# Spring2020.net
KiCad netlist of a schematic drawn in EAGLE
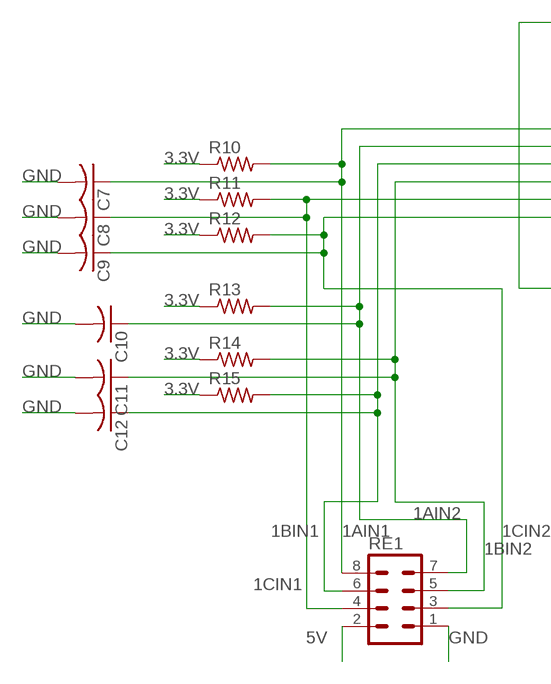
[diagram p0: schematic, sheet 1, part 1 of 2]
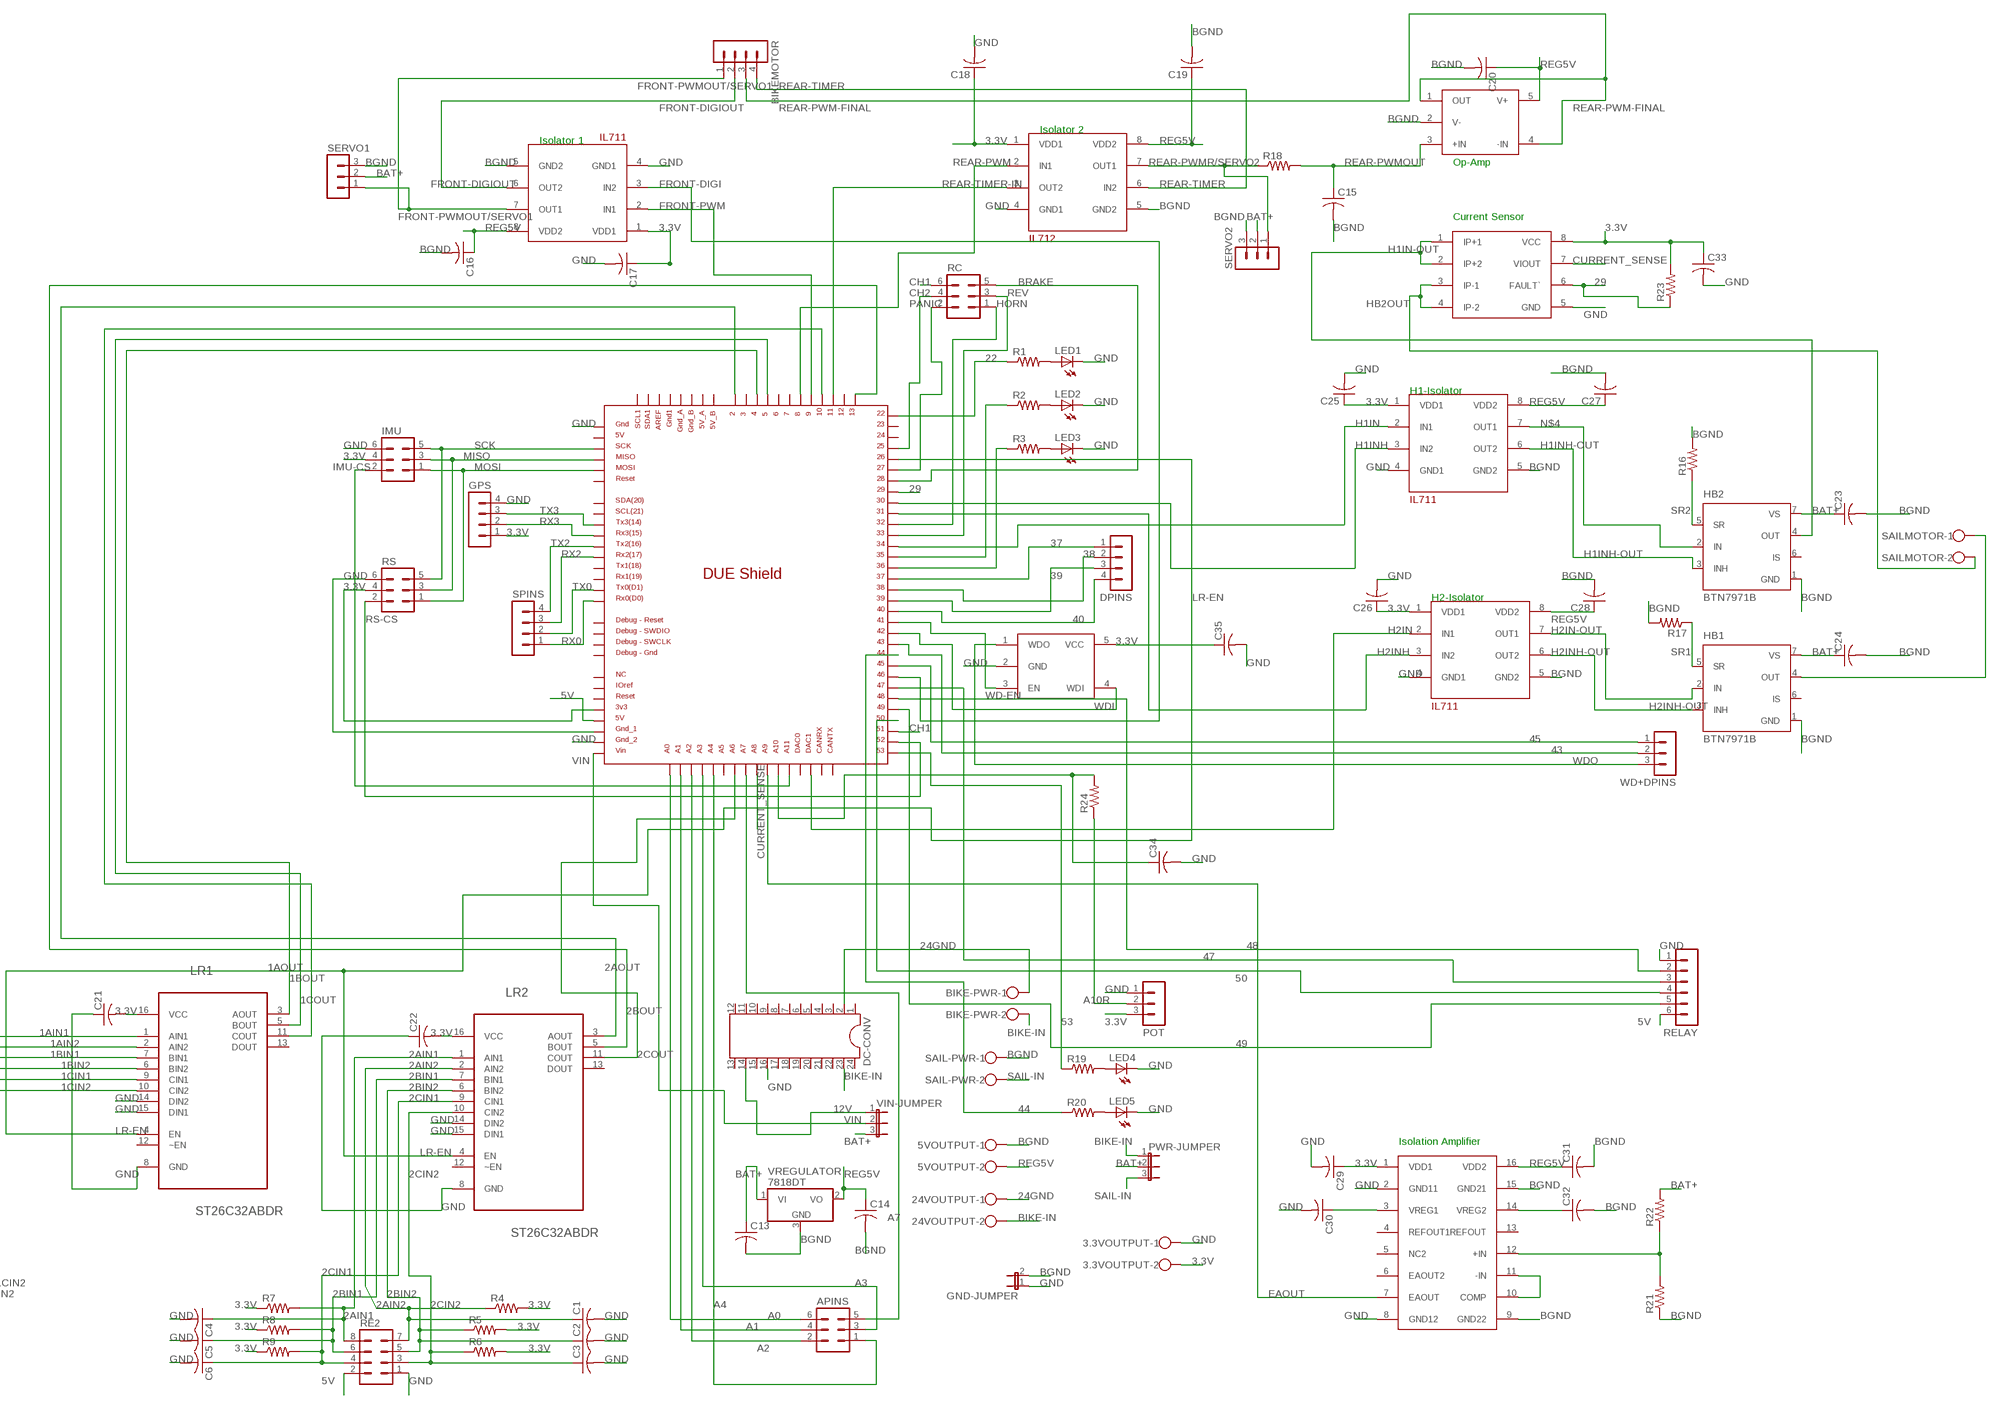
[diagram p1: schematic, sheet 1, part 2 of 2]

(export (version "E")
  (design (tool "Eeschema 10.0.6"))
  (components
    (comp (ref "3.3VOUTPUT")
      (value "W237-102")
      (footprint "eagle-import:W237-102")
      (fields (field (name "MPN") "237-102"))
      (libsource (lib "eagle-import") (part "W237-102"))
    )
    (comp (ref "5VOUTPUT")
      (value "W237-102")
      (footprint "eagle-import:W237-102")
      (fields (field (name "MPN") "237-102"))
      (libsource (lib "eagle-import") (part "W237-102"))
    )
    (comp (ref "24VOUTPUT")
      (value "W237-102")
      (footprint "eagle-import:W237-102")
      (fields (field (name "MPN") "237-102"))
      (libsource (lib "eagle-import") (part "W237-102"))
    )
    (comp (ref "APINS")
      (value "MA03-2")
      (footprint "eagle-import:MA03-2")
      (libsource (lib "eagle-import") (part "MA03-2"))
    )
    (comp (ref "BIKE-PWR")
      (value "W237-102")
      (footprint "eagle-import:W237-102")
      (fields (field (name "MPN") "237-102"))
      (libsource (lib "eagle-import") (part "W237-102"))
    )
    (comp (ref "BIKEMOTOR")
      (value "MA04-1")
      (footprint "eagle-import:MA04-1")
      (libsource (lib "eagle-import") (part "MA04-1"))
    )
    (comp (ref "C1")
      (value "C-US025-025X050")
      (footprint "eagle-import:C025-025X050")
      (libsource (lib "eagle-import") (part "C-US025-025X050"))
    )
    (comp (ref "C2")
      (value "C-US025-025X050")
      (footprint "eagle-import:C025-025X050")
      (libsource (lib "eagle-import") (part "C-US025-025X050"))
    )
    (comp (ref "C3")
      (value "C-US025-025X050")
      (footprint "eagle-import:C025-025X050")
      (libsource (lib "eagle-import") (part "C-US025-025X050"))
    )
    (comp (ref "C4")
      (value "C-US025-025X050")
      (footprint "eagle-import:C025-025X050")
      (libsource (lib "eagle-import") (part "C-US025-025X050"))
    )
    (comp (ref "C5")
      (value "C-US025-025X050")
      (footprint "eagle-import:C025-025X050")
      (libsource (lib "eagle-import") (part "C-US025-025X050"))
    )
    (comp (ref "C6")
      (value "C-US025-025X050")
      (footprint "eagle-import:C025-025X050")
      (libsource (lib "eagle-import") (part "C-US025-025X050"))
    )
    (comp (ref "C7")
      (value "C-US025-025X050")
      (footprint "eagle-import:C025-025X050")
      (libsource (lib "eagle-import") (part "C-US025-025X050"))
    )
    (comp (ref "C8")
      (value "C-US025-025X050")
      (footprint "eagle-import:C025-025X050")
      (libsource (lib "eagle-import") (part "C-US025-025X050"))
    )
    (comp (ref "C9")
      (value "C-US025-025X050")
      (footprint "eagle-import:C025-025X050")
      (libsource (lib "eagle-import") (part "C-US025-025X050"))
    )
    (comp (ref "C10")
      (value "C-US025-025X050")
      (footprint "eagle-import:C025-025X050")
      (libsource (lib "eagle-import") (part "C-US025-025X050"))
    )
    (comp (ref "C11")
      (value "C-US025-025X050")
      (footprint "eagle-import:C025-025X050")
      (libsource (lib "eagle-import") (part "C-US025-025X050"))
    )
    (comp (ref "C12")
      (value "C-US025-025X050")
      (footprint "eagle-import:C025-025X050")
      (libsource (lib "eagle-import") (part "C-US025-025X050"))
    )
    (comp (ref "C13")
      (value "C-US025-050X050")
      (footprint "eagle-import:C025-050X050")
      (libsource (lib "eagle-import") (part "C-US025-050X050"))
    )
    (comp (ref "C14")
      (value "C-US025-050X050")
      (footprint "eagle-import:C025-050X050")
      (libsource (lib "eagle-import") (part "C-US025-050X050"))
    )
    (comp (ref "C15")
      (value "C-US025-050X050")
      (footprint "eagle-import:C025-050X050")
      (libsource (lib "eagle-import") (part "C-US025-050X050"))
    )
    (comp (ref "C16")
      (value "C-US025-050X050")
      (footprint "eagle-import:C025-050X050")
      (libsource (lib "eagle-import") (part "C-US025-050X050"))
    )
    (comp (ref "C17")
      (value "C-US025-050X050")
      (footprint "eagle-import:C025-050X050")
      (libsource (lib "eagle-import") (part "C-US025-050X050"))
    )
    (comp (ref "C18")
      (value "C-US025-050X050")
      (footprint "eagle-import:C025-050X050")
      (libsource (lib "eagle-import") (part "C-US025-050X050"))
    )
    (comp (ref "C19")
      (value "C-US025-050X050")
      (footprint "eagle-import:C025-050X050")
      (libsource (lib "eagle-import") (part "C-US025-050X050"))
    )
    (comp (ref "C20")
      (value "C-US025-050X050")
      (footprint "eagle-import:C025-050X050")
      (libsource (lib "eagle-import") (part "C-US025-050X050"))
    )
    (comp (ref "C21")
      (value "C-US025-050X050")
      (footprint "eagle-import:C025-050X050")
      (libsource (lib "eagle-import") (part "C-US025-050X050"))
    )
    (comp (ref "C22")
      (value "C-US025-050X050")
      (footprint "eagle-import:C025-050X050")
      (libsource (lib "eagle-import") (part "C-US025-050X050"))
    )
    (comp (ref "C23")
      (value "C-US150-091X182")
      (footprint "eagle-import:C150-091X182")
      (libsource (lib "eagle-import") (part "C-US150-091X182"))
    )
    (comp (ref "C24")
      (value "C-US150-091X182")
      (footprint "eagle-import:C150-091X182")
      (libsource (lib "eagle-import") (part "C-US150-091X182"))
    )
    (comp (ref "C25")
      (value "C-US025-050X050")
      (footprint "eagle-import:C025-050X050")
      (libsource (lib "eagle-import") (part "C-US025-050X050"))
    )
    (comp (ref "C26")
      (value "C-US025-050X050")
      (footprint "eagle-import:C025-050X050")
      (libsource (lib "eagle-import") (part "C-US025-050X050"))
    )
    (comp (ref "C27")
      (value "C-US025-050X050")
      (footprint "eagle-import:C025-050X050")
      (libsource (lib "eagle-import") (part "C-US025-050X050"))
    )
    (comp (ref "C28")
      (value "C-US025-050X050")
      (footprint "eagle-import:C025-050X050")
      (libsource (lib "eagle-import") (part "C-US025-050X050"))
    )
    (comp (ref "C29")
      (value "C-US025-050X050")
      (footprint "eagle-import:C025-050X050")
      (libsource (lib "eagle-import") (part "C-US025-050X050"))
    )
    (comp (ref "C30")
      (value "C-US025-050X050")
      (footprint "eagle-import:C025-050X050")
      (libsource (lib "eagle-import") (part "C-US025-050X050"))
    )
    (comp (ref "C31")
      (value "C-US025-050X050")
      (footprint "eagle-import:C025-050X050")
      (libsource (lib "eagle-import") (part "C-US025-050X050"))
    )
    (comp (ref "C32")
      (value "C-US025-050X050")
      (footprint "eagle-import:C025-050X050")
      (libsource (lib "eagle-import") (part "C-US025-050X050"))
    )
    (comp (ref "C33")
      (value "C-US025-050X050")
      (footprint "eagle-import:C025-050X050")
      (libsource (lib "eagle-import") (part "C-US025-050X050"))
    )
    (comp (ref "C34")
      (value "C-US025-050X050")
      (footprint "eagle-import:C025-050X050")
      (libsource (lib "eagle-import") (part "C-US025-050X050"))
    )
    (comp (ref "C35")
      (value "C-US025-025X050")
      (footprint "eagle-import:C025-025X050")
      (libsource (lib "eagle-import") (part "C-US025-025X050"))
    )
    (comp (ref "DC-CONV")
      (value "CU.INC---VAWQ6-Q48-S12H-6")
      (footprint "eagle-import:DIL24-6")
      (libsource (lib "eagle-import") (part "CU.INC---VAWQ6-Q48-S12H-6"))
    )
    (comp (ref "DPINS")
      (value "MA04-1")
      (footprint "eagle-import:MA04-1")
      (libsource (lib "eagle-import") (part "MA04-1"))
    )
    (comp (ref "GND-JUMPER")
      (value "JP1E")
      (footprint "eagle-import:JP1")
      (libsource (lib "eagle-import") (part "JP1E"))
    )
    (comp (ref "GPS")
      (value "MA04-1")
      (footprint "eagle-import:MA04-1")
      (libsource (lib "eagle-import") (part "MA04-1"))
    )
    (comp (ref "HB1")
      (value "BTN7971B")
      (footprint "eagle-import:P-TO263-7-1")
      (libsource (lib "eagle-import") (part "BTN7971B"))
    )
    (comp (ref "HB2")
      (value "BTN7971B")
      (footprint "eagle-import:P-TO263-7-1")
      (libsource (lib "eagle-import") (part "BTN7971B"))
    )
    (comp (ref "IMU")
      (value "MA03-2")
      (footprint "eagle-import:MA03-2")
      (libsource (lib "eagle-import") (part "MA03-2"))
    )
    (comp (ref "LED1")
      (value "LED5MM")
      (footprint "eagle-import:LED5MM")
      (libsource (lib "eagle-import") (part "LED5MM"))
    )
    (comp (ref "LED2")
      (value "LED5MM")
      (footprint "eagle-import:LED5MM")
      (libsource (lib "eagle-import") (part "LED5MM"))
    )
    (comp (ref "LED3")
      (value "LED5MM")
      (footprint "eagle-import:LED5MM")
      (libsource (lib "eagle-import") (part "LED5MM"))
    )
    (comp (ref "LED4")
      (value "LED5MM")
      (footprint "eagle-import:LED5MM")
      (libsource (lib "eagle-import") (part "LED5MM"))
    )
    (comp (ref "LED5")
      (value "LED5MM")
      (footprint "eagle-import:LED5MM")
      (libsource (lib "eagle-import") (part "LED5MM"))
    )
    (comp (ref "LR1")
      (value "ST26C32ABDR")
      (footprint "eagle-import:SOIC127P600X175-16N")
      (libsource (lib "eagle-import") (part "ST26C32ABDR"))
    )
    (comp (ref "LR2")
      (value "ST26C32ABDR")
      (footprint "eagle-import:SOIC127P600X175-16N")
      (libsource (lib "eagle-import") (part "ST26C32ABDR"))
    )
    (comp (ref "OP-AMP")
      (value "OPAMP")
      (footprint "eagle-import:SOT95P280X145-5N")
      (libsource (lib "eagle-import") (part "OPAMP"))
    )
    (comp (ref "POT")
      (value "MA03-1")
      (footprint "eagle-import:MA03-1")
      (libsource (lib "eagle-import") (part "MA03-1"))
    )
    (comp (ref "PWR-JUMPER")
      (value "JP2E")
      (footprint "eagle-import:JP2")
      (libsource (lib "eagle-import") (part "JP2E"))
    )
    (comp (ref "R1")
      (value "R-US_0309/10")
      (footprint "eagle-import:0309_10")
      (libsource (lib "eagle-import") (part "R-US_0309/10"))
    )
    (comp (ref "R2")
      (value "R-US_0309/10")
      (footprint "eagle-import:0309_10")
      (libsource (lib "eagle-import") (part "R-US_0309/10"))
    )
    (comp (ref "R3")
      (value "R-US_0309/10")
      (footprint "eagle-import:0309_10")
      (libsource (lib "eagle-import") (part "R-US_0309/10"))
    )
    (comp (ref "R4")
      (value "R-US_0613/15")
      (footprint "eagle-import:P0613_15")
      (libsource (lib "eagle-import") (part "resistor_R-US_0613/15"))
    )
    (comp (ref "R5")
      (value "R-US_0613/15")
      (footprint "eagle-import:P0613_15")
      (libsource (lib "eagle-import") (part "resistor_R-US_0613/15"))
    )
    (comp (ref "R6")
      (value "R-US_0613/15")
      (footprint "eagle-import:P0613_15")
      (libsource (lib "eagle-import") (part "resistor_R-US_0613/15"))
    )
    (comp (ref "R7")
      (value "R-US_0613/15")
      (footprint "eagle-import:P0613_15")
      (libsource (lib "eagle-import") (part "resistor_R-US_0613/15"))
    )
    (comp (ref "R8")
      (value "R-US_0613/15")
      (footprint "eagle-import:P0613_15")
      (libsource (lib "eagle-import") (part "resistor_R-US_0613/15"))
    )
    (comp (ref "R9")
      (value "R-US_0613/15")
      (footprint "eagle-import:P0613_15")
      (libsource (lib "eagle-import") (part "resistor_R-US_0613/15"))
    )
    (comp (ref "R10")
      (value "R-US_0613/15")
      (footprint "eagle-import:P0613_15")
      (libsource (lib "eagle-import") (part "resistor_R-US_0613/15"))
    )
    (comp (ref "R11")
      (value "R-US_0613/15")
      (footprint "eagle-import:P0613_15")
      (libsource (lib "eagle-import") (part "resistor_R-US_0613/15"))
    )
    (comp (ref "R12")
      (value "R-US_0613/15")
      (footprint "eagle-import:P0613_15")
      (libsource (lib "eagle-import") (part "resistor_R-US_0613/15"))
    )
    (comp (ref "R13")
      (value "R-US_0613/15")
      (footprint "eagle-import:P0613_15")
      (libsource (lib "eagle-import") (part "resistor_R-US_0613/15"))
    )
    (comp (ref "R14")
      (value "R-US_0613/15")
      (footprint "eagle-import:P0613_15")
      (libsource (lib "eagle-import") (part "resistor_R-US_0613/15"))
    )
    (comp (ref "R15")
      (value "R-US_0613/15")
      (footprint "eagle-import:P0613_15")
      (libsource (lib "eagle-import") (part "resistor_R-US_0613/15"))
    )
    (comp (ref "R16")
      (value "R-US_0613/15")
      (footprint "eagle-import:P0613_15")
      (libsource (lib "eagle-import") (part "resistor_R-US_0613/15"))
    )
    (comp (ref "R17")
      (value "R-US_0613/15")
      (footprint "eagle-import:P0613_15")
      (libsource (lib "eagle-import") (part "resistor_R-US_0613/15"))
    )
    (comp (ref "R18")
      (value "R-US_0414/15")
      (footprint "eagle-import:0414_15")
      (libsource (lib "eagle-import") (part "resistor_R-US_0414/15"))
    )
    (comp (ref "R19")
      (value "R-US_0309/10")
      (footprint "eagle-import:0309_10")
      (libsource (lib "eagle-import") (part "R-US_0309/10"))
    )
    (comp (ref "R20")
      (value "R-US_0309/10")
      (footprint "eagle-import:0309_10")
      (libsource (lib "eagle-import") (part "R-US_0309/10"))
    )
    (comp (ref "R21")
      (value "R-US_0414/15")
      (footprint "eagle-import:0414_15")
      (libsource (lib "eagle-import") (part "resistor_R-US_0414/15"))
    )
    (comp (ref "R22")
      (value "R-US_0414/15")
      (footprint "eagle-import:0414_15")
      (libsource (lib "eagle-import") (part "resistor_R-US_0414/15"))
    )
    (comp (ref "R23")
      (value "R-US_0414/15")
      (footprint "eagle-import:0414_15")
      (libsource (lib "eagle-import") (part "resistor_R-US_0414/15"))
    )
    (comp (ref "R24")
      (value "R-US_0414/15")
      (footprint "eagle-import:0414_15")
      (libsource (lib "eagle-import") (part "resistor_R-US_0414/15"))
    )
    (comp (ref "RC")
      (value "MA03-2")
      (footprint "eagle-import:MA03-2")
      (libsource (lib "eagle-import") (part "MA03-2"))
    )
    (comp (ref "RE1")
      (value "MA04-2")
      (footprint "eagle-import:MA04-2")
      (libsource (lib "eagle-import") (part "MA04-2"))
    )
    (comp (ref "RE2")
      (value "MA04-2")
      (footprint "eagle-import:MA04-2")
      (libsource (lib "eagle-import") (part "MA04-2"))
    )
    (comp (ref "RELAY")
      (value "MA06-1")
      (footprint "eagle-import:MA06-1")
      (libsource (lib "eagle-import") (part "MA06-1"))
    )
    (comp (ref "RS")
      (value "MA03-2")
      (footprint "eagle-import:MA03-2")
      (libsource (lib "eagle-import") (part "MA03-2"))
    )
    (comp (ref "SAIL-PWR")
      (value "W237-102")
      (footprint "eagle-import:W237-102")
      (fields (field (name "MPN") "237-102"))
      (libsource (lib "eagle-import") (part "W237-102"))
    )
    (comp (ref "SAILMOTOR")
      (value "W237-102")
      (footprint "eagle-import:W237-102")
      (fields (field (name "MPN") "237-102"))
      (libsource (lib "eagle-import") (part "W237-102"))
    )
    (comp (ref "SERVO1")
      (value "MA03-1")
      (footprint "eagle-import:MA03-1")
      (libsource (lib "eagle-import") (part "MA03-1"))
    )
    (comp (ref "SERVO2")
      (value "MA03-1")
      (footprint "eagle-import:MA03-1")
      (libsource (lib "eagle-import") (part "MA03-1"))
    )
    (comp (ref "SPINS")
      (value "MA04-1")
      (footprint "eagle-import:MA04-1")
      (libsource (lib "eagle-import") (part "MA04-1"))
    )
    (comp (ref "U$1")
      (value "DUE(NORMAL)")
      (footprint "eagle-import:DUE(NORMAL)")
      (libsource (lib "eagle-import") (part "DUE(NORMAL)"))
    )
    (comp (ref "U$2")
      (value "IL-711")
      (footprint "eagle-import:8PINSOIC")
      (libsource (lib "eagle-import") (part "IL-711"))
    )
    (comp (ref "U$3")
      (value "IL-711")
      (footprint "eagle-import:8PINSOIC")
      (libsource (lib "eagle-import") (part "IL-711"))
    )
    (comp (ref "U$4")
      (value "WATCHDOG")
      (footprint "eagle-import:SOT95P280X145-5N")
      (libsource (lib "eagle-import") (part "WATCHDOG"))
    )
    (comp (ref "U$5")
      (value "ISOLATED_ERROR_AMP_ADUM3190")
      (footprint "eagle-import:QSOP16")
      (libsource (lib "eagle-import") (part "ISOLATED_ERROR_AMP_ADUM3190"))
    )
    (comp (ref "U$6")
      (value "IL-711")
      (footprint "eagle-import:8PINSOIC")
      (libsource (lib "eagle-import") (part "IL-711"))
    )
    (comp (ref "U$7")
      (value "IL-712")
      (footprint "eagle-import:8PINSOIC")
      (libsource (lib "eagle-import") (part "IL-712"))
    )
    (comp (ref "U$8")
      (value "LINEAR_CURRENT_SENSOR_ACS711")
      (footprint "eagle-import:SO8")
      (libsource (lib "eagle-import") (part "LINEAR_CURRENT_SENSOR_ACS711"))
    )
    (comp (ref "VIN-JUMPER")
      (value "JP2E")
      (footprint "eagle-import:JP2")
      (libsource (lib "eagle-import") (part "JP2E"))
    )
    (comp (ref "VREGULATOR")
      (value "7818DT")
      (footprint "eagle-import:TO252")
      (libsource (lib "eagle-import") (part "78DT18"))
    )
    (comp (ref "WD+DPINS")
      (value "MA03-1")
      (footprint "eagle-import:MA03-1")
      (libsource (lib "eagle-import") (part "MA03-1"))
    )
  )
  (nets
    (net (code "1") (name "/1AIN1") (class "Default")
      (node (ref "C7") (pin "1") (pinfunction "1_1") (pintype "passive"))
      (node (ref "LR1") (pin "1") (pinfunction "AIN1_1") (pintype "input"))
      (node (ref "R10") (pin "2") (pinfunction "2_2") (pintype "passive"))
      (node (ref "RE1") (pin "8") (pinfunction "8_8") (pintype "passive"))
    )
    (net (code "2") (name "/1AIN2") (class "Default")
      (node (ref "C10") (pin "1") (pinfunction "1_1") (pintype "passive"))
      (node (ref "LR1") (pin "2") (pinfunction "AIN2_2") (pintype "input"))
      (node (ref "R13") (pin "2") (pinfunction "2_2") (pintype "passive"))
      (node (ref "RE1") (pin "7") (pinfunction "7_7") (pintype "passive"))
    )
    (net (code "3") (name "/1AOUT") (class "Default")
      (node (ref "LR1") (pin "3") (pinfunction "AOUT_3") (pintype "output"))
      (node (ref "U$1") (pin "4") (pinfunction "4_4") (pintype "bidirectional"))
    )
    (net (code "4") (name "/1BIN1") (class "Default")
      (node (ref "C12") (pin "1") (pinfunction "1_1") (pintype "passive"))
      (node (ref "LR1") (pin "7") (pinfunction "BIN1_7") (pintype "input"))
      (node (ref "R15") (pin "2") (pinfunction "2_2") (pintype "passive"))
      (node (ref "RE1") (pin "6") (pinfunction "6_6") (pintype "passive"))
    )
    (net (code "5") (name "/1BIN2") (class "Default")
      (node (ref "C11") (pin "1") (pinfunction "1_1") (pintype "passive"))
      (node (ref "LR1") (pin "6") (pinfunction "BIN2_6") (pintype "input"))
      (node (ref "R14") (pin "2") (pinfunction "2_2") (pintype "passive"))
      (node (ref "RE1") (pin "5") (pinfunction "5_5") (pintype "passive"))
    )
    (net (code "6") (name "/1BOUT") (class "Default")
      (node (ref "LR1") (pin "5") (pinfunction "BOUT_5") (pintype "output"))
      (node (ref "U$1") (pin "5") (pinfunction "5_5") (pintype "bidirectional"))
    )
    (net (code "7") (name "/1CIN1") (class "Default")
      (node (ref "C8") (pin "1") (pinfunction "1_1") (pintype "passive"))
      (node (ref "LR1") (pin "9") (pinfunction "CIN1_9") (pintype "input"))
      (node (ref "R11") (pin "2") (pinfunction "2_2") (pintype "passive"))
      (node (ref "RE1") (pin "4") (pinfunction "4_4") (pintype "passive"))
    )
    (net (code "8") (name "/1CIN2") (class "Default")
      (node (ref "C9") (pin "1") (pinfunction "1_1") (pintype "passive"))
      (node (ref "LR1") (pin "10") (pinfunction "CIN2_10") (pintype "input"))
      (node (ref "R12") (pin "2") (pinfunction "2_2") (pintype "passive"))
      (node (ref "RE1") (pin "3") (pinfunction "3_3") (pintype "passive"))
    )
    (net (code "9") (name "/1COUT") (class "Default")
      (node (ref "LR1") (pin "11") (pinfunction "COUT_11") (pintype "output"))
      (node (ref "U$1") (pin "10") (pinfunction "10_10") (pintype "bidirectional"))
    )
    (net (code "10") (name "/2AIN1") (class "Default")
      (node (ref "C4") (pin "1") (pinfunction "1_1") (pintype "passive"))
      (node (ref "LR2") (pin "1") (pinfunction "AIN1_1") (pintype "input"))
      (node (ref "R7") (pin "2") (pinfunction "2_2") (pintype "passive"))
      (node (ref "RE2") (pin "8") (pinfunction "8_8") (pintype "passive"))
    )
    (net (code "11") (name "/2AIN2") (class "Default")
      (node (ref "C1") (pin "1") (pinfunction "1_1") (pintype "passive"))
      (node (ref "LR2") (pin "2") (pinfunction "AIN2_2") (pintype "input"))
      (node (ref "R4") (pin "1") (pinfunction "1_1") (pintype "passive"))
      (node (ref "RE2") (pin "7") (pinfunction "7_7") (pintype "passive"))
    )
    (net (code "12") (name "/2AOUT") (class "Default")
      (node (ref "LR2") (pin "3") (pinfunction "AOUT_3") (pintype "output"))
      (node (ref "U$1") (pin "2") (pinfunction "2_2") (pintype "bidirectional"))
    )
    (net (code "13") (name "/2BIN1") (class "Default")
      (node (ref "C5") (pin "1") (pinfunction "1_1") (pintype "passive"))
      (node (ref "LR2") (pin "7") (pinfunction "BIN1_7") (pintype "input"))
      (node (ref "R8") (pin "2") (pinfunction "2_2") (pintype "passive"))
      (node (ref "RE2") (pin "6") (pinfunction "6_6") (pintype "passive"))
    )
    (net (code "14") (name "/2BIN2") (class "Default")
      (node (ref "C2") (pin "1") (pinfunction "1_1") (pintype "passive"))
      (node (ref "LR2") (pin "6") (pinfunction "BIN2_6") (pintype "input"))
      (node (ref "R5") (pin "1") (pinfunction "1_1") (pintype "passive"))
      (node (ref "RE2") (pin "5") (pinfunction "5_5") (pintype "passive"))
    )
    (net (code "15") (name "/2BOUT") (class "Default")
      (node (ref "LR2") (pin "5") (pinfunction "BOUT_5") (pintype "output"))
      (node (ref "U$1") (pin "13") (pinfunction "13_13") (pintype "bidirectional"))
    )
    (net (code "16") (name "/2CIN1") (class "Default")
      (node (ref "C6") (pin "1") (pinfunction "1_1") (pintype "passive"))
      (node (ref "LR2") (pin "9") (pinfunction "CIN1_9") (pintype "input"))
      (node (ref "R9") (pin "2") (pinfunction "2_2") (pintype "passive"))
      (node (ref "RE2") (pin "4") (pinfunction "4_4") (pintype "passive"))
    )
    (net (code "17") (name "/2CIN2") (class "Default")
      (node (ref "C3") (pin "1") (pinfunction "1_1") (pintype "passive"))
      (node (ref "LR2") (pin "10") (pinfunction "CIN2_10") (pintype "input"))
      (node (ref "R6") (pin "1") (pinfunction "1_1") (pintype "passive"))
      (node (ref "RE2") (pin "3") (pinfunction "3_3") (pintype "passive"))
    )
    (net (code "18") (name "/2COUT") (class "Default")
      (node (ref "LR2") (pin "11") (pinfunction "COUT_11") (pintype "output"))
      (node (ref "U$1") (pin "A6") (pinfunction "A6_A6") (pintype "bidirectional"))
    )
    (net (code "19") (name "/3.3V") (class "Default")
      (node (ref "3.3VOUTPUT") (pin "2") (pinfunction "KL_2") (pintype "passive"))
      (node (ref "C17") (pin "1") (pinfunction "1_1") (pintype "passive"))
      (node (ref "C18") (pin "1") (pinfunction "1_1") (pintype "passive"))
      (node (ref "C21") (pin "2") (pinfunction "2_2") (pintype "passive"))
      (node (ref "C22") (pin "2") (pinfunction "2_2") (pintype "passive"))
      (node (ref "C25") (pin "1") (pinfunction "1_1") (pintype "passive"))
      (node (ref "C26") (pin "1") (pinfunction "1_1") (pintype "passive"))
      (node (ref "C29") (pin "1") (pinfunction "1_1") (pintype "passive"))
      (node (ref "C33") (pin "1") (pinfunction "1_1") (pintype "passive"))
      (node (ref "C35") (pin "1") (pinfunction "1_1") (pintype "passive"))
      (node (ref "GPS") (pin "1") (pinfunction "1_1") (pintype "passive"))
      (node (ref "IMU") (pin "4") (pinfunction "4_4") (pintype "passive"))
      (node (ref "LR1") (pin "16") (pinfunction "VCC_16") (pintype "power_in"))
      (node (ref "LR2") (pin "16") (pinfunction "VCC_16") (pintype "power_in"))
      (node (ref "POT") (pin "3") (pinfunction "3_3") (pintype "passive"))
      (node (ref "R10") (pin "1") (pinfunction "1_1") (pintype "passive"))
      (node (ref "R11") (pin "1") (pinfunction "1_1") (pintype "passive"))
      (node (ref "R12") (pin "1") (pinfunction "1_1") (pintype "passive"))
      (node (ref "R13") (pin "1") (pinfunction "1_1") (pintype "passive"))
      (node (ref "R14") (pin "1") (pinfunction "1_1") (pintype "passive"))
      (node (ref "R15") (pin "1") (pinfunction "1_1") (pintype "passive"))
      (node (ref "R23") (pin "2") (pinfunction "2_2") (pintype "passive"))
      (node (ref "R4") (pin "2") (pinfunction "2_2") (pintype "passive"))
      (node (ref "R5") (pin "2") (pinfunction "2_2") (pintype "passive"))
      (node (ref "R6") (pin "2") (pinfunction "2_2") (pintype "passive"))
      (node (ref "R7") (pin "1") (pinfunction "1_1") (pintype "passive"))
      (node (ref "R8") (pin "1") (pinfunction "1_1") (pintype "passive"))
      (node (ref "R9") (pin "1") (pinfunction "1_1") (pintype "passive"))
      (node (ref "RS") (pin "4") (pinfunction "4_4") (pintype "passive"))
      (node (ref "U$1") (pin "3V3") (pinfunction "3V3_3V3") (pintype "bidirectional"))
      (node (ref "U$2") (pin "1") (pinfunction "VDD1_1") (pintype "power_in"))
      (node (ref "U$3") (pin "1") (pinfunction "VDD1_1") (pintype "power_in"))
      (node (ref "U$4") (pin "5") (pinfunction "VCC_5") (pintype "power_in"))
      (node (ref "U$5") (pin "1") (pinfunction "VDD1_1") (pintype "bidirectional"))
      (node (ref "U$6") (pin "1") (pinfunction "VDD1_1") (pintype "power_in"))
      (node (ref "U$7") (pin "1") (pinfunction "VDD1_1") (pintype "power_in"))
      (node (ref "U$8") (pin "8") (pinfunction "VCC_8") (pintype "bidirectional"))
    )
    (net (code "20") (name "/5V") (class "Default")
      (node (ref "RE1") (pin "2") (pinfunction "2_2") (pintype "passive"))
      (node (ref "RE2") (pin "2") (pinfunction "2_2") (pintype "passive"))
      (node (ref "RELAY") (pin "6") (pinfunction "6_6") (pintype "passive"))
      (node (ref "U$1") (pin "5V") (pinfunction "5V_5V") (pintype "bidirectional"))
    )
    (net (code "21") (name "/12V") (class "Default")
      (node (ref "DC-CONV") (pin "14") (pinfunction "14_14") (pintype "passive"))
      (node (ref "VIN-JUMPER") (pin "1") (pinfunction "1_1") (pintype "passive"))
    )
    (net (code "22") (name "/22") (class "Default")
      (node (ref "R1") (pin "1") (pinfunction "1_1") (pintype "passive"))
      (node (ref "U$1") (pin "22") (pinfunction "22_22") (pintype "bidirectional"))
    )
    (net (code "23") (name "/24GND") (class "Default")
      (node (ref "24VOUTPUT") (pin "1") (pinfunction "KL_1") (pintype "passive"))
      (node (ref "BIKE-PWR") (pin "1") (pinfunction "KL_1") (pintype "passive"))
      (node (ref "DC-CONV") (pin "2") (pinfunction "2_2") (pintype "passive"))
    )
    (net (code "24") (name "/29") (class "Default")
      (node (ref "R23") (pin "1") (pinfunction "1_1") (pintype "passive"))
      (node (ref "U$1") (pin "29") (pinfunction "29_29") (pintype "bidirectional"))
      (node (ref "U$8") (pin "6") (pinfunction "FAULT`_6") (pintype "bidirectional"))
    )
    (net (code "25") (name "/37") (class "Default")
      (node (ref "DPINS") (pin "1") (pinfunction "1_1") (pintype "passive"))
      (node (ref "U$1") (pin "37") (pinfunction "37_37") (pintype "bidirectional"))
    )
    (net (code "26") (name "/38") (class "Default")
      (node (ref "DPINS") (pin "2") (pinfunction "2_2") (pintype "passive"))
      (node (ref "U$1") (pin "38") (pinfunction "38_38") (pintype "bidirectional"))
    )
    (net (code "27") (name "/39") (class "Default")
      (node (ref "DPINS") (pin "3") (pinfunction "3_3") (pintype "passive"))
      (node (ref "U$1") (pin "39") (pinfunction "39_39") (pintype "bidirectional"))
    )
    (net (code "28") (name "/40") (class "Default")
      (node (ref "DPINS") (pin "4") (pinfunction "4_4") (pintype "passive"))
      (node (ref "U$1") (pin "40") (pinfunction "40_40") (pintype "bidirectional"))
    )
    (net (code "29") (name "/43") (class "Default")
      (node (ref "U$1") (pin "43") (pinfunction "43_43") (pintype "bidirectional"))
      (node (ref "WD+DPINS") (pin "2") (pinfunction "2_2") (pintype "passive"))
    )
    (net (code "30") (name "/44") (class "Default")
      (node (ref "R20") (pin "1") (pinfunction "1_1") (pintype "passive"))
      (node (ref "U$1") (pin "44") (pinfunction "44_44") (pintype "bidirectional"))
    )
    (net (code "31") (name "/45") (class "Default")
      (node (ref "U$1") (pin "45") (pinfunction "45_45") (pintype "bidirectional"))
      (node (ref "WD+DPINS") (pin "1") (pinfunction "1_1") (pintype "passive"))
    )
    (net (code "32") (name "/47") (class "Default")
      (node (ref "RELAY") (pin "3") (pinfunction "3_3") (pintype "passive"))
      (node (ref "U$1") (pin "47") (pinfunction "47_47") (pintype "bidirectional"))
    )
    (net (code "33") (name "/48") (class "Default")
      (node (ref "RELAY") (pin "2") (pinfunction "2_2") (pintype "passive"))
      (node (ref "U$1") (pin "48") (pinfunction "48_48") (pintype "bidirectional"))
    )
    (net (code "34") (name "/49") (class "Default")
      (node (ref "RELAY") (pin "5") (pinfunction "5_5") (pintype "passive"))
      (node (ref "U$1") (pin "49") (pinfunction "49_49") (pintype "bidirectional"))
    )
    (net (code "35") (name "/50") (class "Default")
      (node (ref "RELAY") (pin "4") (pinfunction "4_4") (pintype "passive"))
      (node (ref "U$1") (pin "50") (pinfunction "50_50") (pintype "bidirectional"))
    )
    (net (code "36") (name "/53") (class "Default")
      (node (ref "R19") (pin "1") (pinfunction "1_1") (pintype "passive"))
      (node (ref "U$1") (pin "53") (pinfunction "53_53") (pintype "bidirectional"))
    )
    (net (code "37") (name "/A0") (class "Default")
      (node (ref "APINS") (pin "6") (pinfunction "6_6") (pintype "passive"))
      (node (ref "U$1") (pin "A0") (pinfunction "A0_A0") (pintype "bidirectional"))
    )
    (net (code "38") (name "/A1") (class "Default")
      (node (ref "APINS") (pin "4") (pinfunction "4_4") (pintype "passive"))
      (node (ref "U$1") (pin "A1") (pinfunction "A1_A1") (pintype "bidirectional"))
    )
    (net (code "39") (name "/A2") (class "Default")
      (node (ref "APINS") (pin "2") (pinfunction "2_2") (pintype "passive"))
      (node (ref "U$1") (pin "A2") (pinfunction "A2_A2") (pintype "bidirectional"))
    )
    (net (code "40") (name "/A3") (class "Default")
      (node (ref "APINS") (pin "3") (pinfunction "3_3") (pintype "passive"))
      (node (ref "U$1") (pin "A3") (pinfunction "A3_A3") (pintype "bidirectional"))
    )
    (net (code "41") (name "/A4") (class "Default")
      (node (ref "APINS") (pin "1") (pinfunction "1_1") (pintype "passive"))
      (node (ref "U$1") (pin "A4") (pinfunction "A4_A4") (pintype "bidirectional"))
    )
    (net (code "42") (name "/A7") (class "Default")
      (node (ref "APINS") (pin "5") (pinfunction "5_5") (pintype "passive"))
      (node (ref "U$1") (pin "A7") (pinfunction "A7_A7") (pintype "bidirectional"))
    )
    (net (code "43") (name "/A10R") (class "Default")
      (node (ref "POT") (pin "2") (pinfunction "2_2") (pintype "passive"))
      (node (ref "R24") (pin "1") (pinfunction "1_1") (pintype "passive"))
    )
    (net (code "44") (name "/BAT+") (class "Default")
      (node (ref "C13") (pin "1") (pinfunction "1_1") (pintype "passive"))
      (node (ref "C23") (pin "1") (pinfunction "1_1") (pintype "passive"))
      (node (ref "C24") (pin "1") (pinfunction "1_1") (pintype "passive"))
      (node (ref "HB1") (pin "7") (pinfunction "VS_7") (pintype "input"))
      (node (ref "HB2") (pin "7") (pinfunction "VS_7") (pintype "input"))
      (node (ref "PWR-JUMPER") (pin "2") (pinfunction "2_2") (pintype "passive"))
      (node (ref "R22") (pin "2") (pinfunction "2_2") (pintype "passive"))
      (node (ref "SERVO1") (pin "2") (pinfunction "2_2") (pintype "passive"))
      (node (ref "SERVO2") (pin "2") (pinfunction "2_2") (pintype "passive"))
      (node (ref "VIN-JUMPER") (pin "3") (pinfunction "3_3") (pintype "passive"))
      (node (ref "VREGULATOR") (pin "1") (pinfunction "VI_1") (pintype "input"))
    )
    (net (code "45") (name "/BGND") (class "Default")
      (node (ref "5VOUTPUT") (pin "1") (pinfunction "KL_1") (pintype "passive"))
      (node (ref "C13") (pin "2") (pinfunction "2_2") (pintype "passive"))
      (node (ref "C14") (pin "2") (pinfunction "2_2") (pintype "passive"))
      (node (ref "C15") (pin "2") (pinfunction "2_2") (pintype "passive"))
      (node (ref "C16") (pin "2") (pinfunction "2_2") (pintype "passive"))
      (node (ref "C19") (pin "2") (pinfunction "2_2") (pintype "passive"))
      (node (ref "C20") (pin "2") (pinfunction "2_2") (pintype "passive"))
      (node (ref "C23") (pin "2") (pinfunction "2_2") (pintype "passive"))
      (node (ref "C24") (pin "2") (pinfunction "2_2") (pintype "passive"))
      (node (ref "C27") (pin "2") (pinfunction "2_2") (pintype "passive"))
      (node (ref "C28") (pin "2") (pinfunction "2_2") (pintype "passive"))
      (node (ref "C31") (pin "2") (pinfunction "2_2") (pintype "passive"))
      (node (ref "C32") (pin "2") (pinfunction "2_2") (pintype "passive"))
      (node (ref "GND-JUMPER") (pin "2") (pinfunction "2_2") (pintype "passive"))
      (node (ref "HB1") (pin "1") (pinfunction "GND_1") (pintype "power_in"))
      (node (ref "HB2") (pin "1") (pinfunction "GND_1") (pintype "power_in"))
      (node (ref "OP-AMP") (pin "2") (pinfunction "V-_2") (pintype "output"))
      (node (ref "R16") (pin "2") (pinfunction "2_2") (pintype "passive"))
      (node (ref "R17") (pin "2") (pinfunction "2_2") (pintype "passive"))
      (node (ref "R21") (pin "1") (pinfunction "1_1") (pintype "passive"))
      (node (ref "SAIL-PWR") (pin "1") (pinfunction "KL_1") (pintype "passive"))
      (node (ref "SERVO1") (pin "3") (pinfunction "3_3") (pintype "passive"))
      (node (ref "SERVO2") (pin "3") (pinfunction "3_3") (pintype "passive"))
      (node (ref "U$2") (pin "5") (pinfunction "GND2_5") (pintype "power_in"))
      (node (ref "U$3") (pin "5") (pinfunction "GND2_5") (pintype "power_in"))
      (node (ref "U$5") (pin "15") (pinfunction "GND21_15") (pintype "bidirectional"))
      (node (ref "U$5") (pin "9") (pinfunction "GND22_9") (pintype "bidirectional"))
      (node (ref "U$6") (pin "5") (pinfunction "GND2_5") (pintype "power_in"))
      (node (ref "U$7") (pin "5") (pinfunction "GND2_5") (pintype "power_in"))
      (node (ref "VREGULATOR") (pin "3") (pinfunction "GND_3") (pintype "passive"))
    )
    (net (code "46") (name "/BIKE-IN") (class "Default")
      (node (ref "24VOUTPUT") (pin "2") (pinfunction "KL_2") (pintype "passive"))
      (node (ref "BIKE-PWR") (pin "2") (pinfunction "KL_2") (pintype "passive"))
      (node (ref "DC-CONV") (pin "23") (pinfunction "23_23") (pintype "passive"))
      (node (ref "PWR-JUMPER") (pin "1") (pinfunction "1_1") (pintype "passive"))
    )
    (net (code "47") (name "/BRAKE") (class "Default")
      (node (ref "RC") (pin "5") (pinfunction "5_5") (pintype "passive"))
      (node (ref "U$1") (pin "28") (pinfunction "28_28") (pintype "bidirectional"))
    )
    (net (code "48") (name "/CH1") (class "Default")
      (node (ref "RC") (pin "6") (pinfunction "6_6") (pintype "passive"))
      (node (ref "U$1") (pin "51") (pinfunction "51_51") (pintype "bidirectional"))
    )
    (net (code "49") (name "/CH2") (class "Default")
      (node (ref "RC") (pin "4") (pinfunction "4_4") (pintype "passive"))
      (node (ref "U$1") (pin "25") (pinfunction "25_25") (pintype "bidirectional"))
    )
    (net (code "50") (name "/CURRENT_SENSE") (class "Default")
      (node (ref "U$1") (pin "A8") (pinfunction "A8_A8") (pintype "bidirectional"))
      (node (ref "U$8") (pin "7") (pinfunction "VIOUT_7") (pintype "bidirectional"))
    )
    (net (code "51") (name "/EAOUT") (class "Default")
      (node (ref "U$1") (pin "A9") (pinfunction "A9_A9") (pintype "bidirectional"))
      (node (ref "U$5") (pin "7") (pinfunction "EAOUT_7") (pintype "bidirectional"))
    )
    (net (code "52") (name "/FRONT-DIGI") (class "Default")
      (node (ref "U$1") (pin "46") (pinfunction "46_46") (pintype "bidirectional"))
      (node (ref "U$2") (pin "3") (pinfunction "IN2_3") (pintype "input"))
    )
    (net (code "53") (name "/FRONT-DIGIOUT") (class "Default")
      (node (ref "BIKEMOTOR") (pin "2") (pinfunction "2_2") (pintype "passive"))
      (node (ref "U$2") (pin "6") (pinfunction "OUT2_6") (pintype "output"))
    )
    (net (code "54") (name "/FRONT-PWM") (class "Default")
      (node (ref "U$1") (pin "9") (pinfunction "9_9") (pintype "bidirectional"))
      (node (ref "U$2") (pin "2") (pinfunction "IN1_2") (pintype "input"))
    )
    (net (code "55") (name "/FRONT-PWMOUT{slash}SERVO1") (class "Default")
      (node (ref "BIKEMOTOR") (pin "1") (pinfunction "1_1") (pintype "passive"))
      (node (ref "SERVO1") (pin "1") (pinfunction "1_1") (pintype "passive"))
      (node (ref "U$2") (pin "7") (pinfunction "OUT1_7") (pintype "output"))
    )
    (net (code "56") (name "/GND") (class "Default")
      (node (ref "3.3VOUTPUT") (pin "1") (pinfunction "KL_1") (pintype "passive"))
      (node (ref "C1") (pin "2") (pinfunction "2_2") (pintype "passive"))
      (node (ref "C10") (pin "2") (pinfunction "2_2") (pintype "passive"))
      (node (ref "C11") (pin "2") (pinfunction "2_2") (pintype "passive"))
      (node (ref "C12") (pin "2") (pinfunction "2_2") (pintype "passive"))
      (node (ref "C17") (pin "2") (pinfunction "2_2") (pintype "passive"))
      (node (ref "C18") (pin "2") (pinfunction "2_2") (pintype "passive"))
      (node (ref "C2") (pin "2") (pinfunction "2_2") (pintype "passive"))
      (node (ref "C21") (pin "1") (pinfunction "1_1") (pintype "passive"))
      (node (ref "C22") (pin "1") (pinfunction "1_1") (pintype "passive"))
      (node (ref "C25") (pin "2") (pinfunction "2_2") (pintype "passive"))
      (node (ref "C26") (pin "2") (pinfunction "2_2") (pintype "passive"))
      (node (ref "C29") (pin "2") (pinfunction "2_2") (pintype "passive"))
      (node (ref "C3") (pin "2") (pinfunction "2_2") (pintype "passive"))
      (node (ref "C30") (pin "2") (pinfunction "2_2") (pintype "passive"))
      (node (ref "C33") (pin "2") (pinfunction "2_2") (pintype "passive"))
      (node (ref "C34") (pin "2") (pinfunction "2_2") (pintype "passive"))
      (node (ref "C35") (pin "2") (pinfunction "2_2") (pintype "passive"))
      (node (ref "C4") (pin "2") (pinfunction "2_2") (pintype "passive"))
      (node (ref "C5") (pin "2") (pinfunction "2_2") (pintype "passive"))
      (node (ref "C6") (pin "2") (pinfunction "2_2") (pintype "passive"))
      (node (ref "C7") (pin "2") (pinfunction "2_2") (pintype "passive"))
      (node (ref "C8") (pin "2") (pinfunction "2_2") (pintype "passive"))
      (node (ref "C9") (pin "2") (pinfunction "2_2") (pintype "passive"))
      (node (ref "DC-CONV") (pin "16") (pinfunction "16_16") (pintype "passive"))
      (node (ref "GND-JUMPER") (pin "1") (pinfunction "1_1") (pintype "passive"))
      (node (ref "GPS") (pin "4") (pinfunction "4_4") (pintype "passive"))
      (node (ref "IMU") (pin "6") (pinfunction "6_6") (pintype "passive"))
      (node (ref "LED1") (pin "K") (pinfunction "C_K") (pintype "passive"))
      (node (ref "LED2") (pin "K") (pinfunction "C_K") (pintype "passive"))
      (node (ref "LED3") (pin "K") (pinfunction "C_K") (pintype "passive"))
      (node (ref "LED4") (pin "K") (pinfunction "C_K") (pintype "passive"))
      (node (ref "LED5") (pin "K") (pinfunction "C_K") (pintype "passive"))
      (node (ref "LR1") (pin "14") (pinfunction "DIN2_14") (pintype "input"))
      (node (ref "LR1") (pin "15") (pinfunction "DIN1_15") (pintype "input"))
      (node (ref "LR1") (pin "8") (pinfunction "GND_8") (pintype "passive"))
      (node (ref "LR2") (pin "14") (pinfunction "DIN2_14") (pintype "input"))
      (node (ref "LR2") (pin "15") (pinfunction "DIN1_15") (pintype "input"))
      (node (ref "LR2") (pin "8") (pinfunction "GND_8") (pintype "passive"))
      (node (ref "POT") (pin "1") (pinfunction "1_1") (pintype "passive"))
      (node (ref "RE1") (pin "1") (pinfunction "1_1") (pintype "passive"))
      (node (ref "RE2") (pin "1") (pinfunction "1_1") (pintype "passive"))
      (node (ref "RELAY") (pin "1") (pinfunction "1_1") (pintype "passive"))
      (node (ref "RS") (pin "6") (pinfunction "6_6") (pintype "passive"))
      (node (ref "U$1") (pin "5V_ICSP") (pinfunction "5V_ICSP_5V_ICSP") (pintype "bidirectional"))
      (node (ref "U$1") (pin "GND_1") (pinfunction "GND_1_GND_1") (pintype "bidirectional"))
      (node (ref "U$1") (pin "GND_2") (pinfunction "GND_2_GND_2") (pintype "bidirectional"))
      (node (ref "U$2") (pin "4") (pinfunction "GND1_4") (pintype "power_in"))
      (node (ref "U$3") (pin "4") (pinfunction "GND1_4") (pintype "power_in"))
      (node (ref "U$4") (pin "2") (pinfunction "GND_2") (pintype "output"))
      (node (ref "U$5") (pin "2") (pinfunction "GND11_2") (pintype "bidirectional"))
      (node (ref "U$5") (pin "8") (pinfunction "GND12_8") (pintype "bidirectional"))
      (node (ref "U$6") (pin "4") (pinfunction "GND1_4") (pintype "power_in"))
      (node (ref "U$7") (pin "4") (pinfunction "GND1_4") (pintype "power_in"))
      (node (ref "U$8") (pin "5") (pinfunction "GND_5") (pintype "bidirectional"))
    )
    (net (code "57") (name "/H1IN") (class "Default")
      (node (ref "U$1") (pin "34") (pinfunction "34_34") (pintype "bidirectional"))
      (node (ref "U$3") (pin "2") (pinfunction "IN1_2") (pintype "input"))
    )
    (net (code "58") (name "/H1IN-OUT") (class "Default")
      (node (ref "HB2") (pin "4") (pinfunction "OUT_4") (pintype "output"))
      (node (ref "U$8") (pin "1") (pinfunction "IP+1_1") (pintype "bidirectional"))
      (node (ref "U$8") (pin "2") (pinfunction "IP+2_2") (pintype "bidirectional"))
    )
    (net (code "59") (name "/H1INH") (class "Default")
      (node (ref "U$1") (pin "30") (pinfunction "30_30") (pintype "bidirectional"))
      (node (ref "U$3") (pin "3") (pinfunction "IN2_3") (pintype "input"))
    )
    (net (code "60") (name "/H1INH-OUT") (class "Default")
      (node (ref "HB2") (pin "3") (pinfunction "INH_3") (pintype "input"))
      (node (ref "U$3") (pin "6") (pinfunction "OUT2_6") (pintype "output"))
    )
    (net (code "61") (name "/H2IN") (class "Default")
      (node (ref "U$1") (pin "DAC1") (pinfunction "DAC1_DAC1") (pintype "bidirectional"))
      (node (ref "U$6") (pin "2") (pinfunction "IN1_2") (pintype "input"))
    )
    (net (code "62") (name "/H2IN-OUT") (class "Default")
      (node (ref "HB1") (pin "2") (pinfunction "IN_2") (pintype "input"))
      (node (ref "U$6") (pin "7") (pinfunction "OUT1_7") (pintype "output"))
    )
    (net (code "63") (name "/H2INH") (class "Default")
      (node (ref "U$1") (pin "31") (pinfunction "31_31") (pintype "bidirectional"))
      (node (ref "U$6") (pin "3") (pinfunction "IN2_3") (pintype "input"))
    )
    (net (code "64") (name "/H2INH-OUT") (class "Default")
      (node (ref "HB1") (pin "3") (pinfunction "INH_3") (pintype "input"))
      (node (ref "U$6") (pin "6") (pinfunction "OUT2_6") (pintype "output"))
    )
    (net (code "65") (name "/HB2OUT") (class "Default")
      (node (ref "SAILMOTOR") (pin "2") (pinfunction "KL_2") (pintype "passive"))
      (node (ref "U$8") (pin "3") (pinfunction "IP-1_3") (pintype "bidirectional"))
      (node (ref "U$8") (pin "4") (pinfunction "IP-2_4") (pintype "bidirectional"))
    )
    (net (code "66") (name "/HORN") (class "Default")
      (node (ref "RC") (pin "1") (pinfunction "1_1") (pintype "passive"))
      (node (ref "U$1") (pin "32") (pinfunction "32_32") (pintype "bidirectional"))
    )
    (net (code "67") (name "/IMU-CS") (class "Default")
      (node (ref "IMU") (pin "2") (pinfunction "2_2") (pintype "passive"))
      (node (ref "U$1") (pin "A11") (pinfunction "A11_A11") (pintype "bidirectional"))
    )
    (net (code "68") (name "/LR-EN") (class "Default")
      (node (ref "LR1") (pin "4") (pinfunction "EN_4") (pintype "input"))
      (node (ref "LR2") (pin "4") (pinfunction "EN_4") (pintype "input"))
      (node (ref "U$1") (pin "26") (pinfunction "26_26") (pintype "bidirectional"))
    )
    (net (code "69") (name "/MISO") (class "Default")
      (node (ref "IMU") (pin "3") (pinfunction "3_3") (pintype "passive"))
      (node (ref "RS") (pin "3") (pinfunction "3_3") (pintype "passive"))
      (node (ref "U$1") (pin "MISO_ICSP") (pinfunction "MISO_ICSP_MISO_ICSP") (pintype "bidirectional"))
    )
    (net (code "70") (name "/MOSI") (class "Default")
      (node (ref "IMU") (pin "1") (pinfunction "1_1") (pintype "passive"))
      (node (ref "RS") (pin "1") (pinfunction "1_1") (pintype "passive"))
      (node (ref "U$1") (pin "MOSI_ICSP") (pinfunction "MOSI_ICSP_MOSI_ICSP") (pintype "bidirectional"))
    )
    (net (code "71") (name "/N$4") (class "Default")
      (node (ref "HB2") (pin "2") (pinfunction "IN_2") (pintype "input"))
      (node (ref "U$3") (pin "7") (pinfunction "OUT1_7") (pintype "output"))
    )
    (net (code "72") (name "/PANIC") (class "Default")
      (node (ref "RC") (pin "2") (pinfunction "2_2") (pintype "passive"))
      (node (ref "U$1") (pin "27") (pinfunction "27_27") (pintype "bidirectional"))
    )
    (net (code "73") (name "/REAR-PWM") (class "Default")
      (node (ref "U$1") (pin "8") (pinfunction "8_8") (pintype "bidirectional"))
      (node (ref "U$7") (pin "2") (pinfunction "IN1_2") (pintype "input"))
    )
    (net (code "74") (name "/REAR-PWM-FINAL") (class "Default")
      (node (ref "BIKEMOTOR") (pin "3") (pinfunction "3_3") (pintype "passive"))
      (node (ref "OP-AMP") (pin "1") (pinfunction "OUT_1") (pintype "output"))
      (node (ref "OP-AMP") (pin "4") (pinfunction "-IN_4") (pintype "input"))
    )
    (net (code "75") (name "/REAR-PWMOUT") (class "Default")
      (node (ref "C15") (pin "1") (pinfunction "1_1") (pintype "passive"))
      (node (ref "OP-AMP") (pin "3") (pinfunction "+IN_3") (pintype "input"))
      (node (ref "R18") (pin "2") (pinfunction "2_2") (pintype "passive"))
    )
    (net (code "76") (name "/REAR-PWMR{slash}SERVO2") (class "Default")
      (node (ref "R18") (pin "1") (pinfunction "1_1") (pintype "passive"))
      (node (ref "SERVO2") (pin "1") (pinfunction "1_1") (pintype "passive"))
      (node (ref "U$7") (pin "7") (pinfunction "OUT1_7") (pintype "output"))
    )
    (net (code "77") (name "/REAR-TIMER") (class "Default")
      (node (ref "BIKEMOTOR") (pin "4") (pinfunction "4_4") (pintype "passive"))
      (node (ref "U$7") (pin "6") (pinfunction "IN2_6") (pintype "input"))
    )
    (net (code "78") (name "/REAR-TIMER-IN") (class "Default")
      (node (ref "U$1") (pin "11") (pinfunction "11_11") (pintype "bidirectional"))
      (node (ref "U$7") (pin "3") (pinfunction "OUT2_3") (pintype "output"))
    )
    (net (code "79") (name "/REG5V") (class "Default")
      (node (ref "5VOUTPUT") (pin "2") (pinfunction "KL_2") (pintype "passive"))
      (node (ref "C14") (pin "1") (pinfunction "1_1") (pintype "passive"))
      (node (ref "C16") (pin "1") (pinfunction "1_1") (pintype "passive"))
      (node (ref "C19") (pin "1") (pinfunction "1_1") (pintype "passive"))
      (node (ref "C20") (pin "1") (pinfunction "1_1") (pintype "passive"))
      (node (ref "C27") (pin "1") (pinfunction "1_1") (pintype "passive"))
      (node (ref "C28") (pin "1") (pinfunction "1_1") (pintype "passive"))
      (node (ref "C31") (pin "1") (pinfunction "1_1") (pintype "passive"))
      (node (ref "OP-AMP") (pin "5") (pinfunction "V+_5") (pintype "power_in"))
      (node (ref "U$2") (pin "8") (pinfunction "VDD2_8") (pintype "power_in"))
      (node (ref "U$3") (pin "8") (pinfunction "VDD2_8") (pintype "power_in"))
      (node (ref "U$5") (pin "16") (pinfunction "VDD2_16") (pintype "bidirectional"))
      (node (ref "U$6") (pin "8") (pinfunction "VDD2_8") (pintype "power_in"))
      (node (ref "U$7") (pin "8") (pinfunction "VDD2_8") (pintype "power_in"))
      (node (ref "VREGULATOR") (pin "2") (pinfunction "VO_2") (pintype "passive"))
    )
    (net (code "80") (name "/REV") (class "Default")
      (node (ref "RC") (pin "3") (pinfunction "3_3") (pintype "passive"))
      (node (ref "U$1") (pin "33") (pinfunction "33_33") (pintype "bidirectional"))
    )
    (net (code "81") (name "/RS-CS") (class "Default")
      (node (ref "RS") (pin "2") (pinfunction "2_2") (pintype "passive"))
      (node (ref "U$1") (pin "52") (pinfunction "52_52") (pintype "bidirectional"))
    )
    (net (code "82") (name "/RX0") (class "Default")
      (node (ref "SPINS") (pin "1") (pinfunction "1_1") (pintype "passive"))
      (node (ref "U$1") (pin "RX0") (pinfunction "RX0_RX0") (pintype "bidirectional"))
    )
    (net (code "83") (name "/RX2") (class "Default")
      (node (ref "SPINS") (pin "3") (pinfunction "3_3") (pintype "passive"))
      (node (ref "U$1") (pin "RX2") (pinfunction "RX2_RX2") (pintype "bidirectional"))
    )
    (net (code "84") (name "/RX3") (class "Default")
      (node (ref "GPS") (pin "2") (pinfunction "2_2") (pintype "passive"))
      (node (ref "U$1") (pin "RX3") (pinfunction "RX3_RX3") (pintype "bidirectional"))
    )
    (net (code "85") (name "/SAIL-IN") (class "Default")
      (node (ref "PWR-JUMPER") (pin "3") (pinfunction "3_3") (pintype "passive"))
      (node (ref "SAIL-PWR") (pin "2") (pinfunction "KL_2") (pintype "passive"))
    )
    (net (code "86") (name "/SCK") (class "Default")
      (node (ref "IMU") (pin "5") (pinfunction "5_5") (pintype "passive"))
      (node (ref "RS") (pin "5") (pinfunction "5_5") (pintype "passive"))
      (node (ref "U$1") (pin "SCK_ICSP") (pinfunction "SCK_ICSP_SCK_ICSP") (pintype "bidirectional"))
    )
    (net (code "87") (name "/SR1") (class "Default")
      (node (ref "HB1") (pin "5") (pinfunction "SR_5") (pintype "open_collector"))
      (node (ref "R17") (pin "1") (pinfunction "1_1") (pintype "passive"))
    )
    (net (code "88") (name "/SR2") (class "Default")
      (node (ref "HB2") (pin "5") (pinfunction "SR_5") (pintype "open_collector"))
      (node (ref "R16") (pin "1") (pinfunction "1_1") (pintype "passive"))
    )
    (net (code "89") (name "/TX0") (class "Default")
      (node (ref "SPINS") (pin "2") (pinfunction "2_2") (pintype "passive"))
      (node (ref "U$1") (pin "TX0") (pinfunction "TX0_TX0") (pintype "bidirectional"))
    )
    (net (code "90") (name "/TX2") (class "Default")
      (node (ref "SPINS") (pin "4") (pinfunction "4_4") (pintype "passive"))
      (node (ref "U$1") (pin "TX2") (pinfunction "TX2_TX2") (pintype "bidirectional"))
    )
    (net (code "91") (name "/TX3") (class "Default")
      (node (ref "GPS") (pin "3") (pinfunction "3_3") (pintype "passive"))
      (node (ref "U$1") (pin "TX3") (pinfunction "TX3_TX3") (pintype "bidirectional"))
    )
    (net (code "92") (name "/VIN") (class "Default")
      (node (ref "U$1") (pin "VIN") (pinfunction "VIN_VIN") (pintype "bidirectional"))
      (node (ref "VIN-JUMPER") (pin "2") (pinfunction "2_2") (pintype "passive"))
    )
    (net (code "93") (name "/WD-EN") (class "Default")
      (node (ref "U$1") (pin "41") (pinfunction "41_41") (pintype "bidirectional"))
      (node (ref "U$4") (pin "3") (pinfunction "EN_3") (pintype "input"))
    )
    (net (code "94") (name "/WDI") (class "Default")
      (node (ref "U$1") (pin "42") (pinfunction "42_42") (pintype "bidirectional"))
      (node (ref "U$4") (pin "4") (pinfunction "WDI_4") (pintype "input"))
    )
    (net (code "95") (name "/WDO") (class "Default")
      (node (ref "U$4") (pin "1") (pinfunction "WDO_1") (pintype "output"))
      (node (ref "WD+DPINS") (pin "3") (pinfunction "3_3") (pintype "passive"))
    )
    (net (code "96") (name "Net-(C34-Pad1)") (class "Default")
      (node (ref "C34") (pin "1") (pinfunction "1_1") (pintype "passive"))
      (node (ref "R24") (pin "2") (pinfunction "2_2") (pintype "passive"))
      (node (ref "U$1") (pin "A10") (pinfunction "A10_A10") (pintype "bidirectional"))
    )
    (net (code "97") (name "Net-(HB1-OUT)") (class "Default")
      (node (ref "HB1") (pin "4") (pinfunction "OUT_4") (pintype "output"))
      (node (ref "SAILMOTOR") (pin "1") (pinfunction "KL_1") (pintype "passive"))
    )
    (net (code "98") (name "Net-(LED1-PadA)") (class "Default")
      (node (ref "LED1") (pin "A") (pinfunction "A_A") (pintype "passive"))
      (node (ref "R1") (pin "2") (pinfunction "2_2") (pintype "passive"))
    )
    (net (code "99") (name "Net-(LED2-PadA)") (class "Default")
      (node (ref "LED2") (pin "A") (pinfunction "A_A") (pintype "passive"))
      (node (ref "R2") (pin "2") (pinfunction "2_2") (pintype "passive"))
    )
    (net (code "100") (name "Net-(LED3-PadA)") (class "Default")
      (node (ref "LED3") (pin "A") (pinfunction "A_A") (pintype "passive"))
      (node (ref "R3") (pin "2") (pinfunction "2_2") (pintype "passive"))
    )
    (net (code "101") (name "Net-(LED4-PadA)") (class "Default")
      (node (ref "LED4") (pin "A") (pinfunction "A_A") (pintype "passive"))
      (node (ref "R19") (pin "2") (pinfunction "2_2") (pintype "passive"))
    )
    (net (code "102") (name "Net-(LED5-PadA)") (class "Default")
      (node (ref "LED5") (pin "A") (pinfunction "A_A") (pintype "passive"))
      (node (ref "R20") (pin "2") (pinfunction "2_2") (pintype "passive"))
    )
    (net (code "103") (name "Net-(R2-Pad1)") (class "Default")
      (node (ref "R2") (pin "1") (pinfunction "1_1") (pintype "passive"))
      (node (ref "U$1") (pin "35") (pinfunction "35_35") (pintype "bidirectional"))
    )
    (net (code "104") (name "Net-(R3-Pad1)") (class "Default")
      (node (ref "R3") (pin "1") (pinfunction "1_1") (pintype "passive"))
      (node (ref "U$1") (pin "36") (pinfunction "36_36") (pintype "bidirectional"))
    )
    (net (code "105") (name "Net-(U$5-+IN)") (class "Default")
      (node (ref "R21") (pin "2") (pinfunction "2_2") (pintype "passive"))
      (node (ref "R22") (pin "1") (pinfunction "1_1") (pintype "passive"))
      (node (ref "U$5") (pin "12") (pinfunction "+IN_12") (pintype "bidirectional"))
    )
    (net (code "106") (name "Net-(U$5--IN)") (class "Default")
      (node (ref "U$5") (pin "10") (pinfunction "COMP_10") (pintype "bidirectional"))
      (node (ref "U$5") (pin "11") (pinfunction "-IN_11") (pintype "bidirectional"))
    )
    (net (code "107") (name "Net-(U$5-VREG1)") (class "Default")
      (node (ref "C30") (pin "1") (pinfunction "1_1") (pintype "passive"))
      (node (ref "U$5") (pin "3") (pinfunction "VREG1_3") (pintype "bidirectional"))
    )
    (net (code "108") (name "Net-(U$5-VREG2)") (class "Default")
      (node (ref "C32") (pin "1") (pinfunction "1_1") (pintype "passive"))
      (node (ref "U$5") (pin "14") (pinfunction "VREG2_14") (pintype "bidirectional"))
    )
    (net (code "109") (name "unconnected-(DC-CONV-Pad1)") (class "Default")
      (node (ref "DC-CONV") (pin "1") (pinfunction "1_1") (pintype "passive"))
    )
    (net (code "110") (name "unconnected-(DC-CONV-Pad3)") (class "Default")
      (node (ref "DC-CONV") (pin "3") (pinfunction "3_3") (pintype "passive"))
    )
    (net (code "111") (name "unconnected-(DC-CONV-Pad4)") (class "Default")
      (node (ref "DC-CONV") (pin "4") (pinfunction "4_4") (pintype "passive"))
    )
    (net (code "112") (name "unconnected-(DC-CONV-Pad5)") (class "Default")
      (node (ref "DC-CONV") (pin "5") (pinfunction "5_5") (pintype "passive"))
    )
    (net (code "113") (name "unconnected-(DC-CONV-Pad6)") (class "Default")
      (node (ref "DC-CONV") (pin "6") (pinfunction "6_6") (pintype "passive"))
    )
    (net (code "114") (name "unconnected-(DC-CONV-Pad7)") (class "Default")
      (node (ref "DC-CONV") (pin "7") (pinfunction "7_7") (pintype "passive"))
    )
    (net (code "115") (name "unconnected-(DC-CONV-Pad8)") (class "Default")
      (node (ref "DC-CONV") (pin "8") (pinfunction "8_8") (pintype "passive"))
    )
    (net (code "116") (name "unconnected-(DC-CONV-Pad9)") (class "Default")
      (node (ref "DC-CONV") (pin "9") (pinfunction "9_9") (pintype "passive"))
    )
    (net (code "117") (name "unconnected-(DC-CONV-Pad10)") (class "Default")
      (node (ref "DC-CONV") (pin "10") (pinfunction "10_10") (pintype "passive"))
    )
    (net (code "118") (name "unconnected-(DC-CONV-Pad11)") (class "Default")
      (node (ref "DC-CONV") (pin "11") (pinfunction "11_11") (pintype "passive"))
    )
    (net (code "119") (name "unconnected-(DC-CONV-Pad12)") (class "Default")
      (node (ref "DC-CONV") (pin "12") (pinfunction "12_12") (pintype "passive"))
    )
    (net (code "120") (name "unconnected-(DC-CONV-Pad13)") (class "Default")
      (node (ref "DC-CONV") (pin "13") (pinfunction "13_13") (pintype "passive"))
    )
    (net (code "121") (name "unconnected-(DC-CONV-Pad15)") (class "Default")
      (node (ref "DC-CONV") (pin "15") (pinfunction "15_15") (pintype "passive"))
    )
    (net (code "122") (name "unconnected-(DC-CONV-Pad17)") (class "Default")
      (node (ref "DC-CONV") (pin "17") (pinfunction "17_17") (pintype "passive"))
    )
    (net (code "123") (name "unconnected-(DC-CONV-Pad18)") (class "Default")
      (node (ref "DC-CONV") (pin "18") (pinfunction "18_18") (pintype "passive"))
    )
    (net (code "124") (name "unconnected-(DC-CONV-Pad19)") (class "Default")
      (node (ref "DC-CONV") (pin "19") (pinfunction "19_19") (pintype "passive"))
    )
    (net (code "125") (name "unconnected-(DC-CONV-Pad20)") (class "Default")
      (node (ref "DC-CONV") (pin "20") (pinfunction "20_20") (pintype "passive"))
    )
    (net (code "126") (name "unconnected-(DC-CONV-Pad21)") (class "Default")
      (node (ref "DC-CONV") (pin "21") (pinfunction "21_21") (pintype "passive"))
    )
    (net (code "127") (name "unconnected-(DC-CONV-Pad22)") (class "Default")
      (node (ref "DC-CONV") (pin "22") (pinfunction "22_22") (pintype "passive"))
    )
    (net (code "128") (name "unconnected-(DC-CONV-Pad24)") (class "Default")
      (node (ref "DC-CONV") (pin "24") (pinfunction "24_24") (pintype "passive"))
    )
    (net (code "129") (name "unconnected-(HB1-IS-Pad6)") (class "Default")
      (node (ref "HB1") (pin "6") (pinfunction "IS_6") (pintype "output"))
    )
    (net (code "130") (name "unconnected-(HB2-IS-Pad6)") (class "Default")
      (node (ref "HB2") (pin "6") (pinfunction "IS_6") (pintype "output"))
    )
    (net (code "131") (name "unconnected-(LR1-DOUT-Pad13)") (class "Default")
      (node (ref "LR1") (pin "13") (pinfunction "DOUT_13") (pintype "output"))
    )
    (net (code "132") (name "unconnected-(LR1-~{EN}-Pad12)") (class "Default")
      (node (ref "LR1") (pin "12") (pinfunction "~{EN}_12") (pintype "input"))
    )
    (net (code "133") (name "unconnected-(LR2-DOUT-Pad13)") (class "Default")
      (node (ref "LR2") (pin "13") (pinfunction "DOUT_13") (pintype "output"))
    )
    (net (code "134") (name "unconnected-(LR2-~{EN}-Pad12)") (class "Default")
      (node (ref "LR2") (pin "12") (pinfunction "~{EN}_12") (pintype "input"))
    )
    (net (code "135") (name "unconnected-(U$1-Pad3)") (class "Default")
      (node (ref "U$1") (pin "3") (pinfunction "3_3") (pintype "bidirectional"))
    )
    (net (code "136") (name "unconnected-(U$1-Pad5V_A)") (class "Default")
      (node (ref "U$1") (pin "5V_A") (pinfunction "5V_A_5V_A") (pintype "bidirectional"))
    )
    (net (code "137") (name "unconnected-(U$1-Pad5V_B)") (class "Default")
      (node (ref "U$1") (pin "5V_B") (pinfunction "5V_B_5V_B") (pintype "bidirectional"))
    )
    (net (code "138") (name "unconnected-(U$1-Pad6)") (class "Default")
      (node (ref "U$1") (pin "6") (pinfunction "6_6") (pintype "bidirectional"))
    )
    (net (code "139") (name "unconnected-(U$1-Pad7)") (class "Default")
      (node (ref "U$1") (pin "7") (pinfunction "7_7") (pintype "bidirectional"))
    )
    (net (code "140") (name "unconnected-(U$1-Pad12)") (class "Default")
      (node (ref "U$1") (pin "12") (pinfunction "12_12") (pintype "bidirectional"))
    )
    (net (code "141") (name "unconnected-(U$1-Pad23)") (class "Default")
      (node (ref "U$1") (pin "23") (pinfunction "23_23") (pintype "bidirectional"))
    )
    (net (code "142") (name "unconnected-(U$1-Pad24)") (class "Default")
      (node (ref "U$1") (pin "24") (pinfunction "24_24") (pintype "bidirectional"))
    )
    (net (code "143") (name "unconnected-(U$1-PadA5)") (class "Default")
      (node (ref "U$1") (pin "A5") (pinfunction "A5_A5") (pintype "bidirectional"))
    )
    (net (code "144") (name "unconnected-(U$1-PadAREF)") (class "Default")
      (node (ref "U$1") (pin "AREF") (pinfunction "AREF_AREF") (pintype "bidirectional"))
    )
    (net (code "145") (name "unconnected-(U$1-PadCANRX)") (class "Default")
      (node (ref "U$1") (pin "CANRX") (pinfunction "CANRX_CANRX") (pintype "bidirectional"))
    )
    (net (code "146") (name "unconnected-(U$1-PadCANTX)") (class "Default")
      (node (ref "U$1") (pin "CANTX") (pinfunction "CANTX_CANTX") (pintype "bidirectional"))
    )
    (net (code "147") (name "unconnected-(U$1-PadDAC0)") (class "Default")
      (node (ref "U$1") (pin "DAC0") (pinfunction "DAC0_DAC0") (pintype "bidirectional"))
    )
    (net (code "148") (name "unconnected-(U$1-PadGND1)") (class "Default")
      (node (ref "U$1") (pin "GND1") (pinfunction "GND1_GND1") (pintype "bidirectional"))
    )
    (net (code "149") (name "unconnected-(U$1-PadGND_A)") (class "Default")
      (node (ref "U$1") (pin "GND_A") (pinfunction "GND_A_GND_A") (pintype "bidirectional"))
    )
    (net (code "150") (name "unconnected-(U$1-PadGND_B)") (class "Default")
      (node (ref "U$1") (pin "GND_B") (pinfunction "GND_B_GND_B") (pintype "bidirectional"))
    )
    (net (code "151") (name "unconnected-(U$1-PadGND_DEBUG)") (class "Default")
      (node (ref "U$1") (pin "GND_DEBUG") (pinfunction "GND_DEBUG_GND_DEBUG") (pintype "bidirectional"))
    )
    (net (code "152") (name "unconnected-(U$1-PadGND_ICSP)") (class "Default")
      (node (ref "U$1") (pin "GND_ICSP") (pinfunction "GND_ICSP_GND_ICSP") (pintype "bidirectional"))
    )
    (net (code "153") (name "unconnected-(U$1-PadIOREF)") (class "Default")
      (node (ref "U$1") (pin "IOREF") (pinfunction "IOREF_IOREF") (pintype "bidirectional"))
    )
    (net (code "154") (name "unconnected-(U$1-PadNC)") (class "Default")
      (node (ref "U$1") (pin "NC") (pinfunction "NC_NC") (pintype "bidirectional"))
    )
    (net (code "155") (name "unconnected-(U$1-PadRESET)") (class "Default")
      (node (ref "U$1") (pin "RESET") (pinfunction "RESET_RESET") (pintype "bidirectional"))
    )
    (net (code "156") (name "unconnected-(U$1-PadRESET_DEBUG)") (class "Default")
      (node (ref "U$1") (pin "RESET_DEBUG") (pinfunction "RESET_DEBUG_RESET_DEBUG") (pintype "bidirectional"))
    )
    (net (code "157") (name "unconnected-(U$1-PadRESET_ICSP)") (class "Default")
      (node (ref "U$1") (pin "RESET_ICSP") (pinfunction "RESET_ICSP_RESET_ICSP") (pintype "bidirectional"))
    )
    (net (code "158") (name "unconnected-(U$1-PadRX1)") (class "Default")
      (node (ref "U$1") (pin "RX1") (pinfunction "RX1_RX1") (pintype "bidirectional"))
    )
    (net (code "159") (name "unconnected-(U$1-PadSCL)") (class "Default")
      (node (ref "U$1") (pin "SCL") (pinfunction "SCL_SCL") (pintype "bidirectional"))
    )
    (net (code "160") (name "unconnected-(U$1-PadSCL1)") (class "Default")
      (node (ref "U$1") (pin "SCL1") (pinfunction "SCL1_SCL1") (pintype "bidirectional"))
    )
    (net (code "161") (name "unconnected-(U$1-PadSDA)") (class "Default")
      (node (ref "U$1") (pin "SDA") (pinfunction "SDA_SDA") (pintype "bidirectional"))
    )
    (net (code "162") (name "unconnected-(U$1-PadSDA1)") (class "Default")
      (node (ref "U$1") (pin "SDA1") (pinfunction "SDA1_SDA1") (pintype "bidirectional"))
    )
    (net (code "163") (name "unconnected-(U$1-PadSWCLK_DEBUG)") (class "Default")
      (node (ref "U$1") (pin "SWCLK_DEBUG") (pinfunction "SWCLK_DEBUG_SWCLK_DEBUG") (pintype "bidirectional"))
    )
    (net (code "164") (name "unconnected-(U$1-PadSWDIO_DEBUG)") (class "Default")
      (node (ref "U$1") (pin "SWDIO_DEBUG") (pinfunction "SWDIO_DEBUG_SWDIO_DEBUG") (pintype "bidirectional"))
    )
    (net (code "165") (name "unconnected-(U$1-PadTX1)") (class "Default")
      (node (ref "U$1") (pin "TX1") (pinfunction "TX1_TX1") (pintype "bidirectional"))
    )
    (net (code "166") (name "unconnected-(U$5-EAOUT2-Pad6)") (class "Default")
      (node (ref "U$5") (pin "6") (pinfunction "EAOUT2_6") (pintype "bidirectional"))
    )
    (net (code "167") (name "unconnected-(U$5-NC2-Pad5)") (class "Default")
      (node (ref "U$5") (pin "5") (pinfunction "NC2_5") (pintype "bidirectional"))
    )
    (net (code "168") (name "unconnected-(U$5-REFOUT-Pad13)") (class "Default")
      (node (ref "U$5") (pin "13") (pinfunction "REFOUT_13") (pintype "bidirectional"))
    )
    (net (code "169") (name "unconnected-(U$5-REFOUT1-Pad4)") (class "Default")
      (node (ref "U$5") (pin "4") (pinfunction "REFOUT1_4") (pintype "bidirectional"))
    )
  )
)
